# pico.net
KiCad netlist of a schematic drawn in Altium Designer
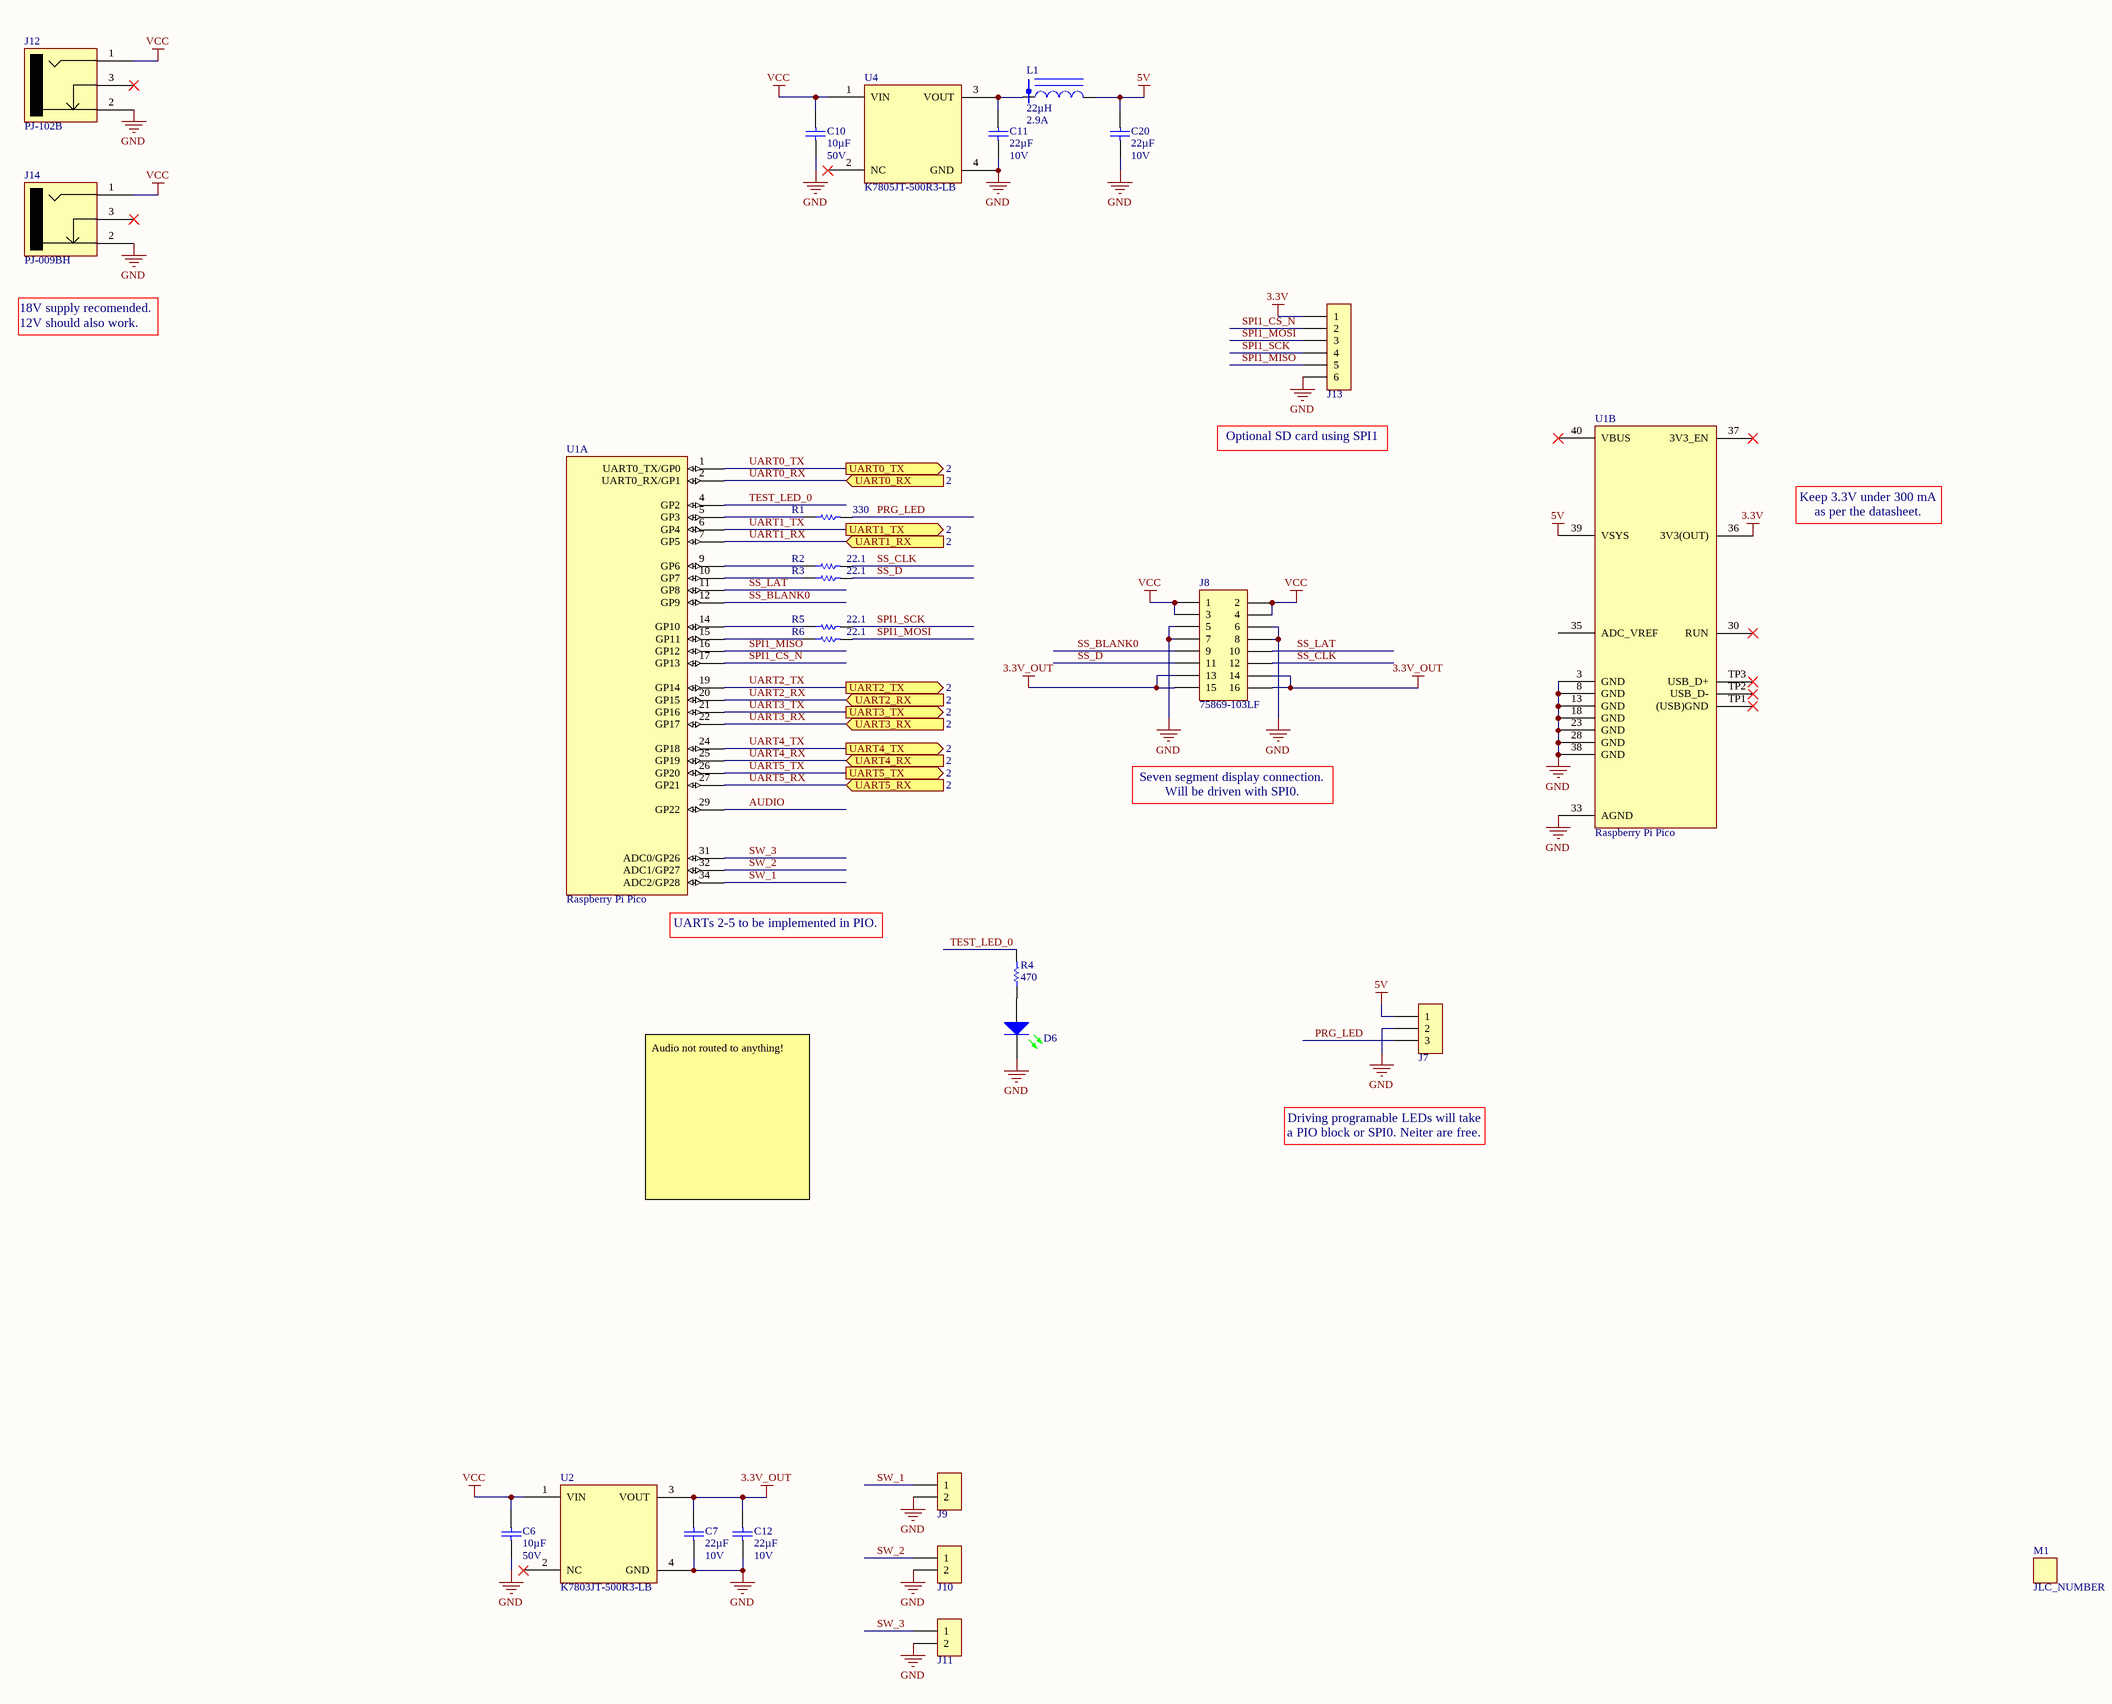
[diagram p0: pico.SchDoc]

(export (version "E")
  (design (tool "Eeschema 10.0.6"))
  (components
    (comp (ref "C6")
      (value "10µF")
      (footprint "Chip1206")
      (description "CAP CER 10UF 50V 10% X5R 1206")
      (fields
        (field (name "VOLTAGE") "50V")
        (field (name "PARTNUMBER") "C3216X5R1H106K160AB")
        (field (name "MANUFACTURER") "TDK Corporation")
      )
      (libsource (lib "Passives") (part "CAP"))
    )
    (comp (ref "C7")
      (value "22µF")
      (footprint "Chip0805")
      (description "CAP CER 22UF 10V 20% X5R 0805")
      (fields
        (field (name "VOLTAGE") "10V")
        (field (name "PARTNUMBER") "C2012X5R1A226M085AC")
        (field (name "MANUFACTURER") "TDK Corporation")
      )
      (libsource (lib "Passives") (part "CAP"))
    )
    (comp (ref "C10")
      (value "10µF")
      (footprint "Chip1206")
      (description "CAP CER 10UF 50V 10% X5R 1206")
      (fields
        (field (name "VOLTAGE") "50V")
        (field (name "PARTNUMBER") "C3216X5R1H106K160AB")
        (field (name "MANUFACTURER") "TDK Corporation")
      )
      (libsource (lib "Passives") (part "CAP"))
    )
    (comp (ref "C11")
      (value "22µF")
      (footprint "Chip0805")
      (description "CAP CER 22UF 10V 20% X5R 0805")
      (fields
        (field (name "VOLTAGE") "10V")
        (field (name "PARTNUMBER") "C2012X5R1A226M085AC")
        (field (name "MANUFACTURER") "TDK Corporation")
      )
      (libsource (lib "Passives") (part "CAP"))
    )
    (comp (ref "C12")
      (value "22µF")
      (footprint "Chip0805")
      (description "CAP CER 22UF 10V 20% X5R 0805")
      (fields
        (field (name "VOLTAGE") "10V")
        (field (name "PARTNUMBER") "C2012X5R1A226M085AC")
        (field (name "MANUFACTURER") "TDK Corporation")
      )
      (libsource (lib "Passives") (part "CAP"))
    )
    (comp (ref "C20")
      (value "22µF")
      (footprint "Chip0805")
      (description "CAP CER 22UF 10V 20% X5R 0805")
      (fields
        (field (name "VOLTAGE") "10V")
        (field (name "PARTNUMBER") "C2012X5R1A226M085AC")
        (field (name "MANUFACTURER") "TDK Corporation")
      )
      (libsource (lib "Passives") (part "CAP"))
    )
    (comp (ref "D6")
      (value "GREEN")
      (footprint "LED0603")
      (description "LED GREEN CLEAR THIN 0603 SMD")
      (fields (field (name "PARTNUMBER") "LTST-C191GKT") (field (name "MANUFACTURER") "Lite-On Inc"))
      (libsource (lib "Optoelectronics") (part "LED_GREEN"))
    )
    (comp (ref "J7")
      (value "3-644456-3")
      (footprint "TE_3-644456-3")
      (description "CONN HEADER VERT 3POS .100 TIN")
      (fields (field (name "MANUFACTURER") "TE Connectivity"))
      (libsource (lib "Connectors") (part "HEADER_1x3"))
    )
    (comp (ref "J8")
      (value "75869-103LF")
      (footprint "IDC_100_2x8")
      (description "CONN HEADER 16POS DUAL VERT PCB")
      (fields (field (name "MANUFACTURER") "FCI"))
      (libsource (lib "Connectors") (part "HEADER_2x8_ALT"))
    )
    (comp (ref "J9")
      (value "B2B-XH-A")
      (footprint "JST_B2B-XH-A")
      (description "CONN HEADER VERT 2POS 2.5MM")
      (fields (field (name "MANUFACTURER") "JST Sales America Inc."))
      (libsource (lib "Connectors") (part "HEADER_1x2"))
    )
    (comp (ref "J10")
      (value "B2B-XH-A")
      (footprint "JST_B2B-XH-A")
      (description "CONN HEADER VERT 2POS 2.5MM")
      (fields (field (name "MANUFACTURER") "JST Sales America Inc."))
      (libsource (lib "Connectors") (part "HEADER_1x2"))
    )
    (comp (ref "J11")
      (value "B2B-XH-A")
      (footprint "JST_B2B-XH-A")
      (description "CONN HEADER VERT 2POS 2.5MM")
      (fields (field (name "MANUFACTURER") "JST Sales America Inc."))
      (libsource (lib "Connectors") (part "HEADER_1x2"))
    )
    (comp (ref "J12")
      (value "PJ-102B")
      (footprint "CUI_PJ-102B")
      (description "CONN PWR JACK 2.5X5.5MM SOLDER")
      (fields (field (name "MANUFACTURER") "CUI Devices"))
      (libsource (lib "Connectors") (part "DC_POWER_JACK"))
    )
    (comp (ref "J13")
      (value "3-644456-6")
      (footprint "TE_3-644456-6")
      (description "CONN HEADER VERT 6POS .100 TIN")
      (fields (field (name "MANUFACTURER") "TE Connectivity"))
      (libsource (lib "Connectors") (part "HEADER_1x6"))
    )
    (comp (ref "J14")
      (value "PJ-009BH")
      (footprint "CUI_PJ-009BH")
      (description "CONN PWR JACK 2.5X5.5MM SOLDER")
      (fields (field (name "MANUFACTURER") "CUI Devices"))
      (libsource (lib "Connectors") (part "DC_POWER_JACK"))
    )
    (comp (ref "L1")
      (value "22µH")
      (footprint "Sumida_CDRH105R")
      (description "INDUCTOR POWER 22UH 2.95A SMD")
      (fields
        (field (name "CURRENT RATING") "2.9A")
        (field (name "PARTNUMBER") "CDRH105RNP-220NC")
        (field (name "MANUFACTURER") "Sumida America Components Inc")
      )
      (libsource (lib "Passives") (part "IND_SHIELDED"))
    )
    (comp (ref "M1")
      (value "JLC_NUMBER")
      (footprint "JLC_NUMBER")
      (description "JLC Order Number Location")
      (libsource (lib "Mechanical") (part "MECH_NO_BOM"))
    )
    (comp (ref "R1")
      (value "330")
      (footprint "Chip0805")
      (description "RES 330 OHM 1/8W 1% 0805 SMD")
      (fields (field (name "PARTNUMBER") "CRCW0805330RFKEA") (field (name "MANUFACTURER") "Vishay Dale"))
      (libsource (lib "Passives") (part "RES"))
    )
    (comp (ref "R2")
      (value "22.1")
      (footprint "Chip0805")
      (description "RES 22.1 OHM 1/8W 1% 0805 SMD")
      (fields (field (name "PARTNUMBER") "CRCW080522R1FKEA") (field (name "MANUFACTURER") "Vishay Dale"))
      (libsource (lib "Passives") (part "RES"))
    )
    (comp (ref "R3")
      (value "22.1")
      (footprint "Chip0805")
      (description "RES 22.1 OHM 1/8W 1% 0805 SMD")
      (fields (field (name "PARTNUMBER") "CRCW080522R1FKEA") (field (name "MANUFACTURER") "Vishay Dale"))
      (libsource (lib "Passives") (part "RES"))
    )
    (comp (ref "R4")
      (value "470")
      (footprint "Chip0805")
      (description "RES 470 OHM 1/8W 1% 0805 SMD")
      (fields (field (name "PARTNUMBER") "CRCW0805470RFKEA") (field (name "MANUFACTURER") "Vishay Dale"))
      (libsource (lib "Passives") (part "RES"))
    )
    (comp (ref "R5")
      (value "22.1")
      (footprint "Chip0805")
      (description "RES 22.1 OHM 1/8W 1% 0805 SMD")
      (fields (field (name "PARTNUMBER") "CRCW080522R1FKEA") (field (name "MANUFACTURER") "Vishay Dale"))
      (libsource (lib "Passives") (part "RES"))
    )
    (comp (ref "R6")
      (value "22.1")
      (footprint "Chip0805")
      (description "RES 22.1 OHM 1/8W 1% 0805 SMD")
      (fields (field (name "PARTNUMBER") "CRCW080522R1FKEA") (field (name "MANUFACTURER") "Vishay Dale"))
      (libsource (lib "Passives") (part "RES"))
    )
    (comp (ref "U1")
      (value "Raspberry Pi Pico")
      (footprint "RASPBERRY_PI_PICO")
      (description "RASPBERRY PI PICO RP2040 BOARD")
      (fields (field (name "MANUFACTURER PART NUMBER") "SC0915") (field (name "MANUFACTURER") "Raspberry Pi"))
      (libsource (lib "ICs") (part "PI_PICO_SC0915"))
    )
    (comp (ref "U2")
      (value "K7803JT-500R3-LB")
      (footprint "MORNSUN_K78XXJT-500R3-LB")
      (description "LINEAR REGULATOR REPLACEMENT DC")
      (fields (field (name "MANUFACTURER") "Mornsun America, LLC"))
      (libsource (lib "ICs") (part "MORNSUN_K78XXJT-500R3-LB"))
    )
    (comp (ref "U4")
      (value "K7805JT-500R3-LB")
      (footprint "MORNSUN_K78XXJT-500R3-LB")
      (description "LINEAR REGULATOR REPLACEMENT DC")
      (fields (field (name "MANUFACTURER") "Mornsun America, LLC"))
      (libsource (lib "ICs") (part "MORNSUN_K78XXJT-500R3-LB"))
    )
  )
  (nets
    (net (code "1") (name "/AUDIO") (class "Default")
      (node (ref "U1") (pin "29") (pinfunction "GP22_29") (pintype "bidirectional"))
    )
    (net (code "2") (name "/PRG_LED") (class "Default")
      (node (ref "J7") (pin "3") (pinfunction "3_3") (pintype "passive"))
      (node (ref "R1") (pin "2") (pinfunction "2_2") (pintype "passive"))
    )
    (net (code "3") (name "/SPI1_CS_N") (class "Default")
      (node (ref "J13") (pin "2") (pinfunction "2_2") (pintype "passive"))
      (node (ref "U1") (pin "17") (pinfunction "GP13_17") (pintype "bidirectional"))
    )
    (net (code "4") (name "/SPI1_MISO") (class "Default")
      (node (ref "J13") (pin "5") (pinfunction "5_5") (pintype "passive"))
      (node (ref "U1") (pin "16") (pinfunction "GP12_16") (pintype "bidirectional"))
    )
    (net (code "5") (name "/SPI1_MOSI") (class "Default")
      (node (ref "J13") (pin "3") (pinfunction "3_3") (pintype "passive"))
      (node (ref "R6") (pin "2") (pinfunction "2_2") (pintype "passive"))
    )
    (net (code "6") (name "/SPI1_SCK") (class "Default")
      (node (ref "J13") (pin "4") (pinfunction "4_4") (pintype "passive"))
      (node (ref "R5") (pin "2") (pinfunction "2_2") (pintype "passive"))
    )
    (net (code "7") (name "/SS_BLANK0") (class "Default")
      (node (ref "J8") (pin "9") (pinfunction "9_9") (pintype "passive"))
      (node (ref "U1") (pin "12") (pinfunction "GP9_12") (pintype "bidirectional"))
    )
    (net (code "8") (name "/SS_CLK") (class "Default")
      (node (ref "J8") (pin "12") (pinfunction "12_12") (pintype "passive"))
      (node (ref "R2") (pin "2") (pinfunction "2_2") (pintype "passive"))
    )
    (net (code "9") (name "/SS_D") (class "Default")
      (node (ref "J8") (pin "11") (pinfunction "11_11") (pintype "passive"))
      (node (ref "R3") (pin "2") (pinfunction "2_2") (pintype "passive"))
    )
    (net (code "10") (name "/SS_LAT") (class "Default")
      (node (ref "J8") (pin "10") (pinfunction "10_10") (pintype "passive"))
      (node (ref "U1") (pin "11") (pinfunction "GP8_11") (pintype "bidirectional"))
    )
    (net (code "11") (name "/SW_1") (class "Default")
      (node (ref "J9") (pin "1") (pinfunction "1_1") (pintype "passive"))
      (node (ref "U1") (pin "34") (pinfunction "ADC2/GP28_34") (pintype "bidirectional"))
    )
    (net (code "12") (name "/SW_2") (class "Default")
      (node (ref "J10") (pin "1") (pinfunction "1_1") (pintype "passive"))
      (node (ref "U1") (pin "32") (pinfunction "ADC1/GP27_32") (pintype "bidirectional"))
    )
    (net (code "13") (name "/SW_3") (class "Default")
      (node (ref "J11") (pin "1") (pinfunction "1_1") (pintype "passive"))
      (node (ref "U1") (pin "31") (pinfunction "ADC0/GP26_31") (pintype "bidirectional"))
    )
    (net (code "14") (name "/TEST_LED_0") (class "Default")
      (node (ref "R4") (pin "2") (pinfunction "2_2") (pintype "passive"))
      (node (ref "U1") (pin "4") (pinfunction "GP2_4") (pintype "bidirectional"))
    )
    (net (code "15") (name "/UART0_RX") (class "Default")
      (node (ref "U1") (pin "2") (pinfunction "UART0_RX/GP1_2") (pintype "bidirectional"))
    )
    (net (code "16") (name "/UART0_TX") (class "Default")
      (node (ref "U1") (pin "1") (pinfunction "UART0_TX/GP0_1") (pintype "bidirectional"))
    )
    (net (code "17") (name "/UART1_RX") (class "Default")
      (node (ref "U1") (pin "7") (pinfunction "GP5_7") (pintype "bidirectional"))
    )
    (net (code "18") (name "/UART1_TX") (class "Default")
      (node (ref "U1") (pin "6") (pinfunction "GP4_6") (pintype "bidirectional"))
    )
    (net (code "19") (name "/UART2_RX") (class "Default")
      (node (ref "U1") (pin "20") (pinfunction "GP15_20") (pintype "bidirectional"))
    )
    (net (code "20") (name "/UART2_TX") (class "Default")
      (node (ref "U1") (pin "19") (pinfunction "GP14_19") (pintype "bidirectional"))
    )
    (net (code "21") (name "/UART3_RX") (class "Default")
      (node (ref "U1") (pin "22") (pinfunction "GP17_22") (pintype "bidirectional"))
    )
    (net (code "22") (name "/UART3_TX") (class "Default")
      (node (ref "U1") (pin "21") (pinfunction "GP16_21") (pintype "bidirectional"))
    )
    (net (code "23") (name "/UART4_RX") (class "Default")
      (node (ref "U1") (pin "25") (pinfunction "GP19_25") (pintype "bidirectional"))
    )
    (net (code "24") (name "/UART4_TX") (class "Default")
      (node (ref "U1") (pin "24") (pinfunction "GP18_24") (pintype "bidirectional"))
    )
    (net (code "25") (name "/UART5_RX") (class "Default")
      (node (ref "U1") (pin "27") (pinfunction "GP21_27") (pintype "bidirectional"))
    )
    (net (code "26") (name "/UART5_TX") (class "Default")
      (node (ref "U1") (pin "26") (pinfunction "GP20_26") (pintype "bidirectional"))
    )
    (net (code "27") (name "3.3V") (class "Default")
      (node (ref "J13") (pin "1") (pinfunction "1_1") (pintype "passive"))
      (node (ref "U1") (pin "36") (pinfunction "3V3(OUT)_36") (pintype "passive"))
    )
    (net (code "28") (name "3.3V_OUT") (class "Default")
      (node (ref "C12") (pin "2") (pinfunction "2_2") (pintype "passive"))
      (node (ref "C7") (pin "2") (pinfunction "2_2") (pintype "passive"))
      (node (ref "J8") (pin "13") (pinfunction "13_13") (pintype "passive"))
      (node (ref "J8") (pin "14") (pinfunction "14_14") (pintype "passive"))
      (node (ref "J8") (pin "15") (pinfunction "15_15") (pintype "passive"))
      (node (ref "J8") (pin "16") (pinfunction "16_16") (pintype "passive"))
      (node (ref "U2") (pin "3") (pinfunction "VOUT_3") (pintype "passive"))
    )
    (net (code "29") (name "5V") (class "Default")
      (node (ref "C20") (pin "2") (pinfunction "2_2") (pintype "passive"))
      (node (ref "J7") (pin "1") (pinfunction "1_1") (pintype "passive"))
      (node (ref "L1") (pin "2") (pinfunction "2_2") (pintype "passive"))
      (node (ref "U1") (pin "39") (pinfunction "VSYS_39") (pintype "passive"))
    )
    (net (code "30") (name "GND") (class "Default")
      (node (ref "C10") (pin "1") (pinfunction "1_1") (pintype "passive"))
      (node (ref "C11") (pin "1") (pinfunction "1_1") (pintype "passive"))
      (node (ref "C12") (pin "1") (pinfunction "1_1") (pintype "passive"))
      (node (ref "C20") (pin "1") (pinfunction "1_1") (pintype "passive"))
      (node (ref "C6") (pin "1") (pinfunction "1_1") (pintype "passive"))
      (node (ref "C7") (pin "1") (pinfunction "1_1") (pintype "passive"))
      (node (ref "D6") (pin "2") (pinfunction "C_2") (pintype "passive"))
      (node (ref "J10") (pin "2") (pinfunction "2_2") (pintype "passive"))
      (node (ref "J11") (pin "2") (pinfunction "2_2") (pintype "passive"))
      (node (ref "J12") (pin "2") (pinfunction "2_2") (pintype "passive"))
      (node (ref "J13") (pin "6") (pinfunction "6_6") (pintype "passive"))
      (node (ref "J14") (pin "2") (pinfunction "2_2") (pintype "passive"))
      (node (ref "J7") (pin "2") (pinfunction "2_2") (pintype "passive"))
      (node (ref "J8") (pin "5") (pinfunction "5_5") (pintype "passive"))
      (node (ref "J8") (pin "6") (pinfunction "6_6") (pintype "passive"))
      (node (ref "J8") (pin "7") (pinfunction "7_7") (pintype "passive"))
      (node (ref "J8") (pin "8") (pinfunction "8_8") (pintype "passive"))
      (node (ref "J9") (pin "2") (pinfunction "2_2") (pintype "passive"))
      (node (ref "U1") (pin "13") (pinfunction "GND_13") (pintype "passive"))
      (node (ref "U1") (pin "18") (pinfunction "GND_18") (pintype "passive"))
      (node (ref "U1") (pin "23") (pinfunction "GND_23") (pintype "passive"))
      (node (ref "U1") (pin "28") (pinfunction "GND_28") (pintype "passive"))
      (node (ref "U1") (pin "3") (pinfunction "GND_3") (pintype "passive"))
      (node (ref "U1") (pin "33") (pinfunction "AGND_33") (pintype "passive"))
      (node (ref "U1") (pin "38") (pinfunction "GND_38") (pintype "passive"))
      (node (ref "U1") (pin "8") (pinfunction "GND_8") (pintype "passive"))
      (node (ref "U2") (pin "4") (pinfunction "GND_4") (pintype "passive"))
      (node (ref "U4") (pin "4") (pinfunction "GND_4") (pintype "passive"))
    )
    (net (code "31") (name "Net-(D6-A)") (class "Default")
      (node (ref "D6") (pin "1") (pinfunction "A_1") (pintype "passive"))
      (node (ref "R4") (pin "1") (pinfunction "1_1") (pintype "passive"))
    )
    (net (code "32") (name "Net-(U1A-GP3)") (class "Default")
      (node (ref "R1") (pin "1") (pinfunction "1_1") (pintype "passive"))
      (node (ref "U1") (pin "5") (pinfunction "GP3_5") (pintype "bidirectional"))
    )
    (net (code "33") (name "Net-(U1A-GP6)") (class "Default")
      (node (ref "R2") (pin "1") (pinfunction "1_1") (pintype "passive"))
      (node (ref "U1") (pin "9") (pinfunction "GP6_9") (pintype "bidirectional"))
    )
    (net (code "34") (name "Net-(U1A-GP7)") (class "Default")
      (node (ref "R3") (pin "1") (pinfunction "1_1") (pintype "passive"))
      (node (ref "U1") (pin "10") (pinfunction "GP7_10") (pintype "bidirectional"))
    )
    (net (code "35") (name "Net-(U1A-GP10)") (class "Default")
      (node (ref "R5") (pin "1") (pinfunction "1_1") (pintype "passive"))
      (node (ref "U1") (pin "14") (pinfunction "GP10_14") (pintype "bidirectional"))
    )
    (net (code "36") (name "Net-(U1A-GP11)") (class "Default")
      (node (ref "R6") (pin "1") (pinfunction "1_1") (pintype "passive"))
      (node (ref "U1") (pin "15") (pinfunction "GP11_15") (pintype "bidirectional"))
    )
    (net (code "37") (name "Net-(U4-VOUT)") (class "Default")
      (node (ref "C11") (pin "2") (pinfunction "2_2") (pintype "passive"))
      (node (ref "L1") (pin "1") (pinfunction "1_1") (pintype "passive"))
      (node (ref "U4") (pin "3") (pinfunction "VOUT_3") (pintype "passive"))
    )
    (net (code "38") (name "VCC") (class "Default")
      (node (ref "C10") (pin "2") (pinfunction "2_2") (pintype "passive"))
      (node (ref "C6") (pin "2") (pinfunction "2_2") (pintype "passive"))
      (node (ref "J12") (pin "1") (pinfunction "1_1") (pintype "passive"))
      (node (ref "J14") (pin "1") (pinfunction "1_1") (pintype "passive"))
      (node (ref "J8") (pin "1") (pinfunction "1_1") (pintype "passive"))
      (node (ref "J8") (pin "2") (pinfunction "2_2") (pintype "passive"))
      (node (ref "J8") (pin "3") (pinfunction "3_3") (pintype "passive"))
      (node (ref "J8") (pin "4") (pinfunction "4_4") (pintype "passive"))
      (node (ref "U2") (pin "1") (pinfunction "VIN_1") (pintype "passive"))
      (node (ref "U4") (pin "1") (pinfunction "VIN_1") (pintype "passive"))
    )
    (net (code "39") (name "unconnected-(J12-Pad3)") (class "Default")
      (node (ref "J12") (pin "3") (pinfunction "3_3") (pintype "passive+no_connect"))
    )
    (net (code "40") (name "unconnected-(J14-Pad3)") (class "Default")
      (node (ref "J14") (pin "3") (pinfunction "3_3") (pintype "passive+no_connect"))
    )
    (net (code "41") (name "unconnected-(U1B-(USB)GND-PadTP1)") (class "Default")
      (node (ref "U1") (pin "TP1") (pinfunction "(USB)GND_TP1") (pintype "passive+no_connect"))
    )
    (net (code "42") (name "unconnected-(U1B-3V3_EN-Pad37)") (class "Default")
      (node (ref "U1") (pin "37") (pinfunction "3V3_EN_37") (pintype "passive+no_connect"))
    )
    (net (code "43") (name "unconnected-(U1B-ADC_VREF-Pad35)") (class "Default")
      (node (ref "U1") (pin "35") (pinfunction "ADC_VREF_35") (pintype "passive"))
    )
    (net (code "44") (name "unconnected-(U1B-RUN-Pad30)") (class "Default")
      (node (ref "U1") (pin "30") (pinfunction "RUN_30") (pintype "passive+no_connect"))
    )
    (net (code "45") (name "unconnected-(U1B-USB_D+-PadTP3)") (class "Default")
      (node (ref "U1") (pin "TP3") (pinfunction "USB_D+_TP3") (pintype "passive+no_connect"))
    )
    (net (code "46") (name "unconnected-(U1B-USB_D--PadTP2)") (class "Default")
      (node (ref "U1") (pin "TP2") (pinfunction "USB_D-_TP2") (pintype "passive+no_connect"))
    )
    (net (code "47") (name "unconnected-(U1B-VBUS-Pad40)") (class "Default")
      (node (ref "U1") (pin "40") (pinfunction "VBUS_40") (pintype "passive+no_connect"))
    )
    (net (code "48") (name "unconnected-(U2-NC-Pad2)") (class "Default")
      (node (ref "U2") (pin "2") (pinfunction "NC_2") (pintype "passive+no_connect"))
    )
    (net (code "49") (name "unconnected-(U4-NC-Pad2)") (class "Default")
      (node (ref "U4") (pin "2") (pinfunction "NC_2") (pintype "passive+no_connect"))
    )
  )
)
